# homecomputer-6502.net
KiCad netlist of a schematic drawn in EAGLE
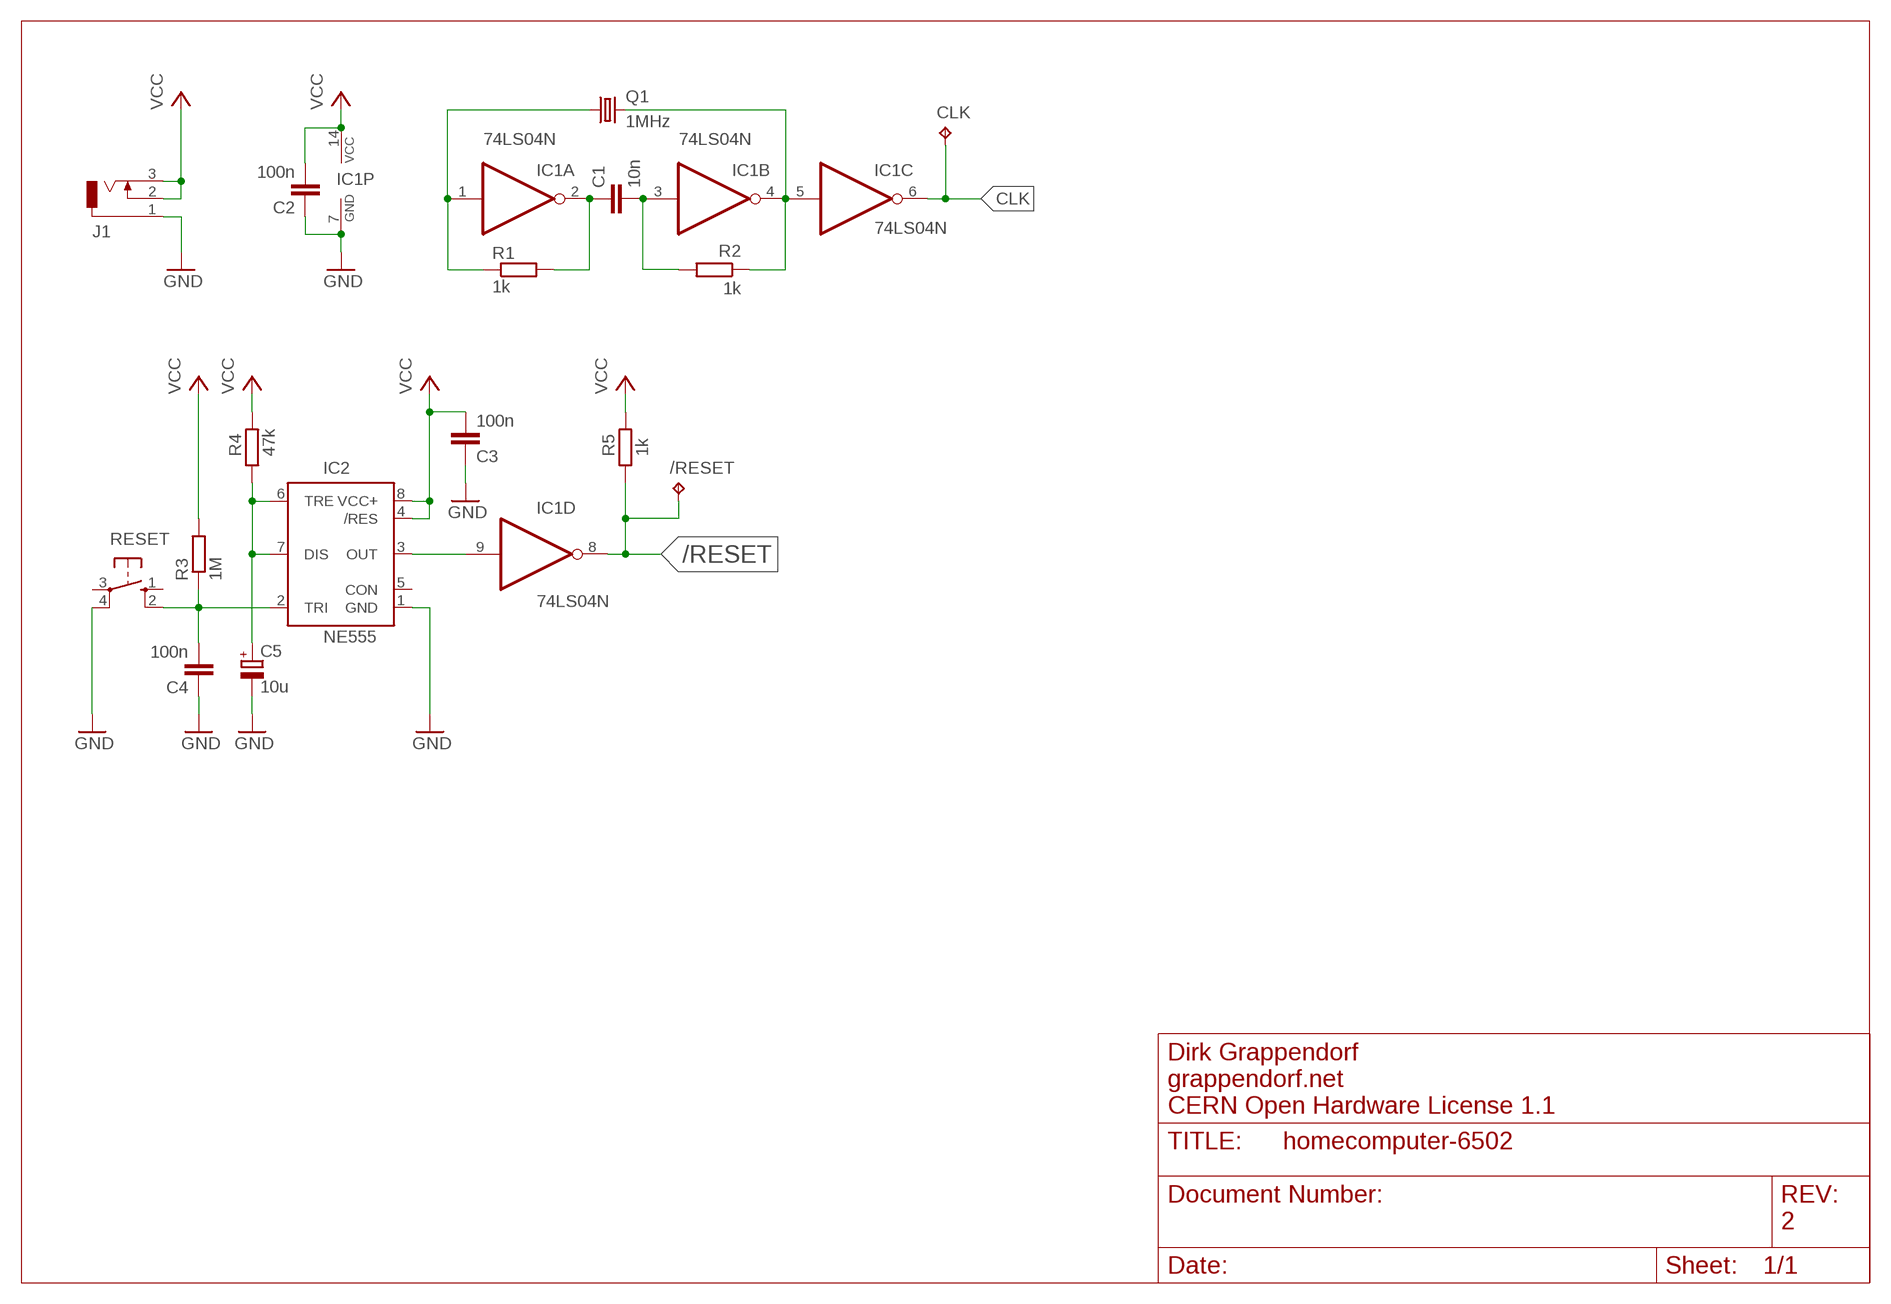
[diagram p0: schematic, sheet 1]

(export (version "E")
  (design (tool "Eeschema 10.0.6"))
  (components
    (comp (ref "/RESET")
      (value "TPTP15SQ")
      (footprint "eagle-import:TP15SQ")
      (libsource (lib "eagle-import") (part "TPTP15SQ"))
    )
    (comp (ref "C1")
      (value "10n")
      (footprint "eagle-import:C025-024X044")
      (libsource (lib "eagle-import") (part "C-EU025-024X044"))
    )
    (comp (ref "C2")
      (value "100n")
      (footprint "eagle-import:C025-024X044")
      (libsource (lib "eagle-import") (part "C-EU025-024X044"))
    )
    (comp (ref "C3")
      (value "100n")
      (footprint "eagle-import:C025-024X044")
      (libsource (lib "eagle-import") (part "C-EU025-024X044"))
    )
    (comp (ref "C4")
      (value "100n")
      (footprint "eagle-import:C025-024X044")
      (libsource (lib "eagle-import") (part "C-EU025-024X044"))
    )
    (comp (ref "C5")
      (value "10u")
      (footprint "eagle-import:E2,5-6E")
      (libsource (lib "eagle-import") (part "CPOL-EUE2,5-6E"))
    )
    (comp (ref "CLK")
      (value "TPTP15SQ")
      (footprint "eagle-import:TP15SQ")
      (libsource (lib "eagle-import") (part "TPTP15SQ"))
    )
    (comp (ref "IC1")
      (value "74LS04N")
      (footprint "eagle-import:DIL14")
      (libsource (lib "eagle-import") (part "7404NLS"))
    )
    (comp (ref "IC2")
      (value "NE555")
      (footprint "eagle-import:DIL-08")
      (fields (field (name "MF") "Arrow Electronics") (field (name "MPN") "NE555N"))
      (libsource (lib "eagle-import") (part "NE555"))
    )
    (comp (ref "J1")
      (value "DCJ0303")
      (footprint "eagle-import:DCJ0303")
      (libsource (lib "eagle-import") (part "DCJ0303"))
    )
    (comp (ref "Q1")
      (value "1MHz")
      (footprint "eagle-import:HC49U-V")
      (libsource (lib "eagle-import") (part "CRYSTALHC49U-V"))
    )
    (comp (ref "R1")
      (value "1k")
      (footprint "eagle-import:0204_5")
      (libsource (lib "eagle-import") (part "R-EU_0204/5"))
    )
    (comp (ref "R2")
      (value "1k")
      (footprint "eagle-import:0204_5")
      (libsource (lib "eagle-import") (part "R-EU_0204/5"))
    )
    (comp (ref "R3")
      (value "1M")
      (footprint "eagle-import:0204_5")
      (libsource (lib "eagle-import") (part "R-EU_0204/5"))
    )
    (comp (ref "R4")
      (value "47k")
      (footprint "eagle-import:0204_5")
      (libsource (lib "eagle-import") (part "R-EU_0204/5"))
    )
    (comp (ref "R5")
      (value "1k")
      (footprint "eagle-import:0204_5")
      (libsource (lib "eagle-import") (part "R-EU_0204/5"))
    )
    (comp (ref "RESET")
      (value "10-XX")
      (footprint "eagle-import:B3F-10XX")
      (fields (field (name "MPN") "B3F-1000"))
      (libsource (lib "eagle-import") (part "10-XX"))
    )
  )
  (nets
    (net (code "1") (name "CLK") (class "Default")
      (node (ref "CLK") (pin "TP") (pinfunction "TP_TP") (pintype "input"))
      (node (ref "IC1") (pin "6") (pinfunction "O_6") (pintype "output"))
    )
    (net (code "2") (name "GND") (class "Default")
      (node (ref "C2") (pin "1") (pinfunction "1_1") (pintype "passive"))
      (node (ref "C3") (pin "1") (pinfunction "1_1") (pintype "passive"))
      (node (ref "C4") (pin "1") (pinfunction "1_1") (pintype "passive"))
      (node (ref "C5") (pin "-") (pinfunction "-_-") (pintype "passive"))
      (node (ref "IC1") (pin "7") (pinfunction "GND_7") (pintype "power_in"))
      (node (ref "IC2") (pin "1") (pinfunction "GND_1") (pintype "power_in"))
      (node (ref "J1") (pin "1") (pinfunction "1_1") (pintype "passive"))
      (node (ref "RESET") (pin "4") (pinfunction "P1_4") (pintype "passive"))
    )
    (net (code "3") (name "Net-(IC1A-I)") (class "Default")
      (node (ref "IC1") (pin "1") (pinfunction "I_1") (pintype "input"))
      (node (ref "Q1") (pin "1") (pinfunction "1_1") (pintype "passive"))
      (node (ref "R1") (pin "1") (pinfunction "1_1") (pintype "passive"))
    )
    (net (code "4") (name "Net-(IC1A-O)") (class "Default")
      (node (ref "C1") (pin "1") (pinfunction "1_1") (pintype "passive"))
      (node (ref "IC1") (pin "2") (pinfunction "O_2") (pintype "output"))
      (node (ref "R1") (pin "2") (pinfunction "2_2") (pintype "passive"))
    )
    (net (code "5") (name "Net-(IC1B-I)") (class "Default")
      (node (ref "C1") (pin "2") (pinfunction "2_2") (pintype "passive"))
      (node (ref "IC1") (pin "3") (pinfunction "I_3") (pintype "input"))
      (node (ref "R2") (pin "2") (pinfunction "2_2") (pintype "passive"))
    )
    (net (code "6") (name "Net-(IC1B-O)") (class "Default")
      (node (ref "IC1") (pin "4") (pinfunction "O_4") (pintype "output"))
      (node (ref "IC1") (pin "5") (pinfunction "I_5") (pintype "input"))
      (node (ref "Q1") (pin "2") (pinfunction "2_2") (pintype "passive"))
      (node (ref "R2") (pin "1") (pinfunction "1_1") (pintype "passive"))
    )
    (net (code "7") (name "Net-(IC1D-I)") (class "Default")
      (node (ref "IC1") (pin "9") (pinfunction "I_9") (pintype "input"))
      (node (ref "IC2") (pin "3") (pinfunction "OUT_3") (pintype "output"))
    )
    (net (code "8") (name "Net-(IC2-DIS)") (class "Default")
      (node (ref "C5") (pin "+") (pinfunction "+_+") (pintype "passive"))
      (node (ref "IC2") (pin "6") (pinfunction "TRE_6") (pintype "input"))
      (node (ref "IC2") (pin "7") (pinfunction "DIS_7") (pintype "input"))
      (node (ref "R4") (pin "1") (pinfunction "1_1") (pintype "passive"))
    )
    (net (code "9") (name "Net-(IC2-TRI)") (class "Default")
      (node (ref "C4") (pin "2") (pinfunction "2_2") (pintype "passive"))
      (node (ref "IC2") (pin "2") (pinfunction "TRI_2") (pintype "input"))
      (node (ref "R3") (pin "1") (pinfunction "1_1") (pintype "passive"))
      (node (ref "RESET") (pin "2") (pinfunction "S1_2") (pintype "passive"))
    )
    (net (code "10") (name "VCC") (class "Default")
      (node (ref "C2") (pin "2") (pinfunction "2_2") (pintype "passive"))
      (node (ref "C3") (pin "2") (pinfunction "2_2") (pintype "passive"))
      (node (ref "IC1") (pin "14") (pinfunction "VCC_14") (pintype "power_in"))
      (node (ref "IC2") (pin "4") (pinfunction "/RES_4") (pintype "input"))
      (node (ref "IC2") (pin "8") (pinfunction "VCC+_8") (pintype "power_in"))
      (node (ref "J1") (pin "2") (pinfunction "2_2") (pintype "passive"))
      (node (ref "J1") (pin "3") (pinfunction "3_3") (pintype "passive"))
      (node (ref "R3") (pin "2") (pinfunction "2_2") (pintype "passive"))
      (node (ref "R4") (pin "2") (pinfunction "2_2") (pintype "passive"))
      (node (ref "R5") (pin "2") (pinfunction "2_2") (pintype "passive"))
    )
    (net (code "11") (name "unconnected-(IC2-CON-Pad5)") (class "Default")
      (node (ref "IC2") (pin "5") (pinfunction "CON_5") (pintype "input"))
    )
    (net (code "12") (name "unconnected-(RESET-P-Pad3)") (class "Default")
      (node (ref "RESET") (pin "3") (pinfunction "P_3") (pintype "passive"))
    )
    (net (code "13") (name "unconnected-(RESET-S-Pad1)") (class "Default")
      (node (ref "RESET") (pin "1") (pinfunction "S_1") (pintype "passive"))
    )
    (net (code "14") (name "{slash}RESET") (class "Default")
      (node (ref "/RESET") (pin "TP") (pinfunction "TP_TP") (pintype "input"))
      (node (ref "IC1") (pin "8") (pinfunction "O_8") (pintype "output"))
      (node (ref "R5") (pin "1") (pinfunction "1_1") (pintype "passive"))
    )
  )
)
